# esp-oled-thing.net
KiCad netlist of a schematic drawn in EAGLE
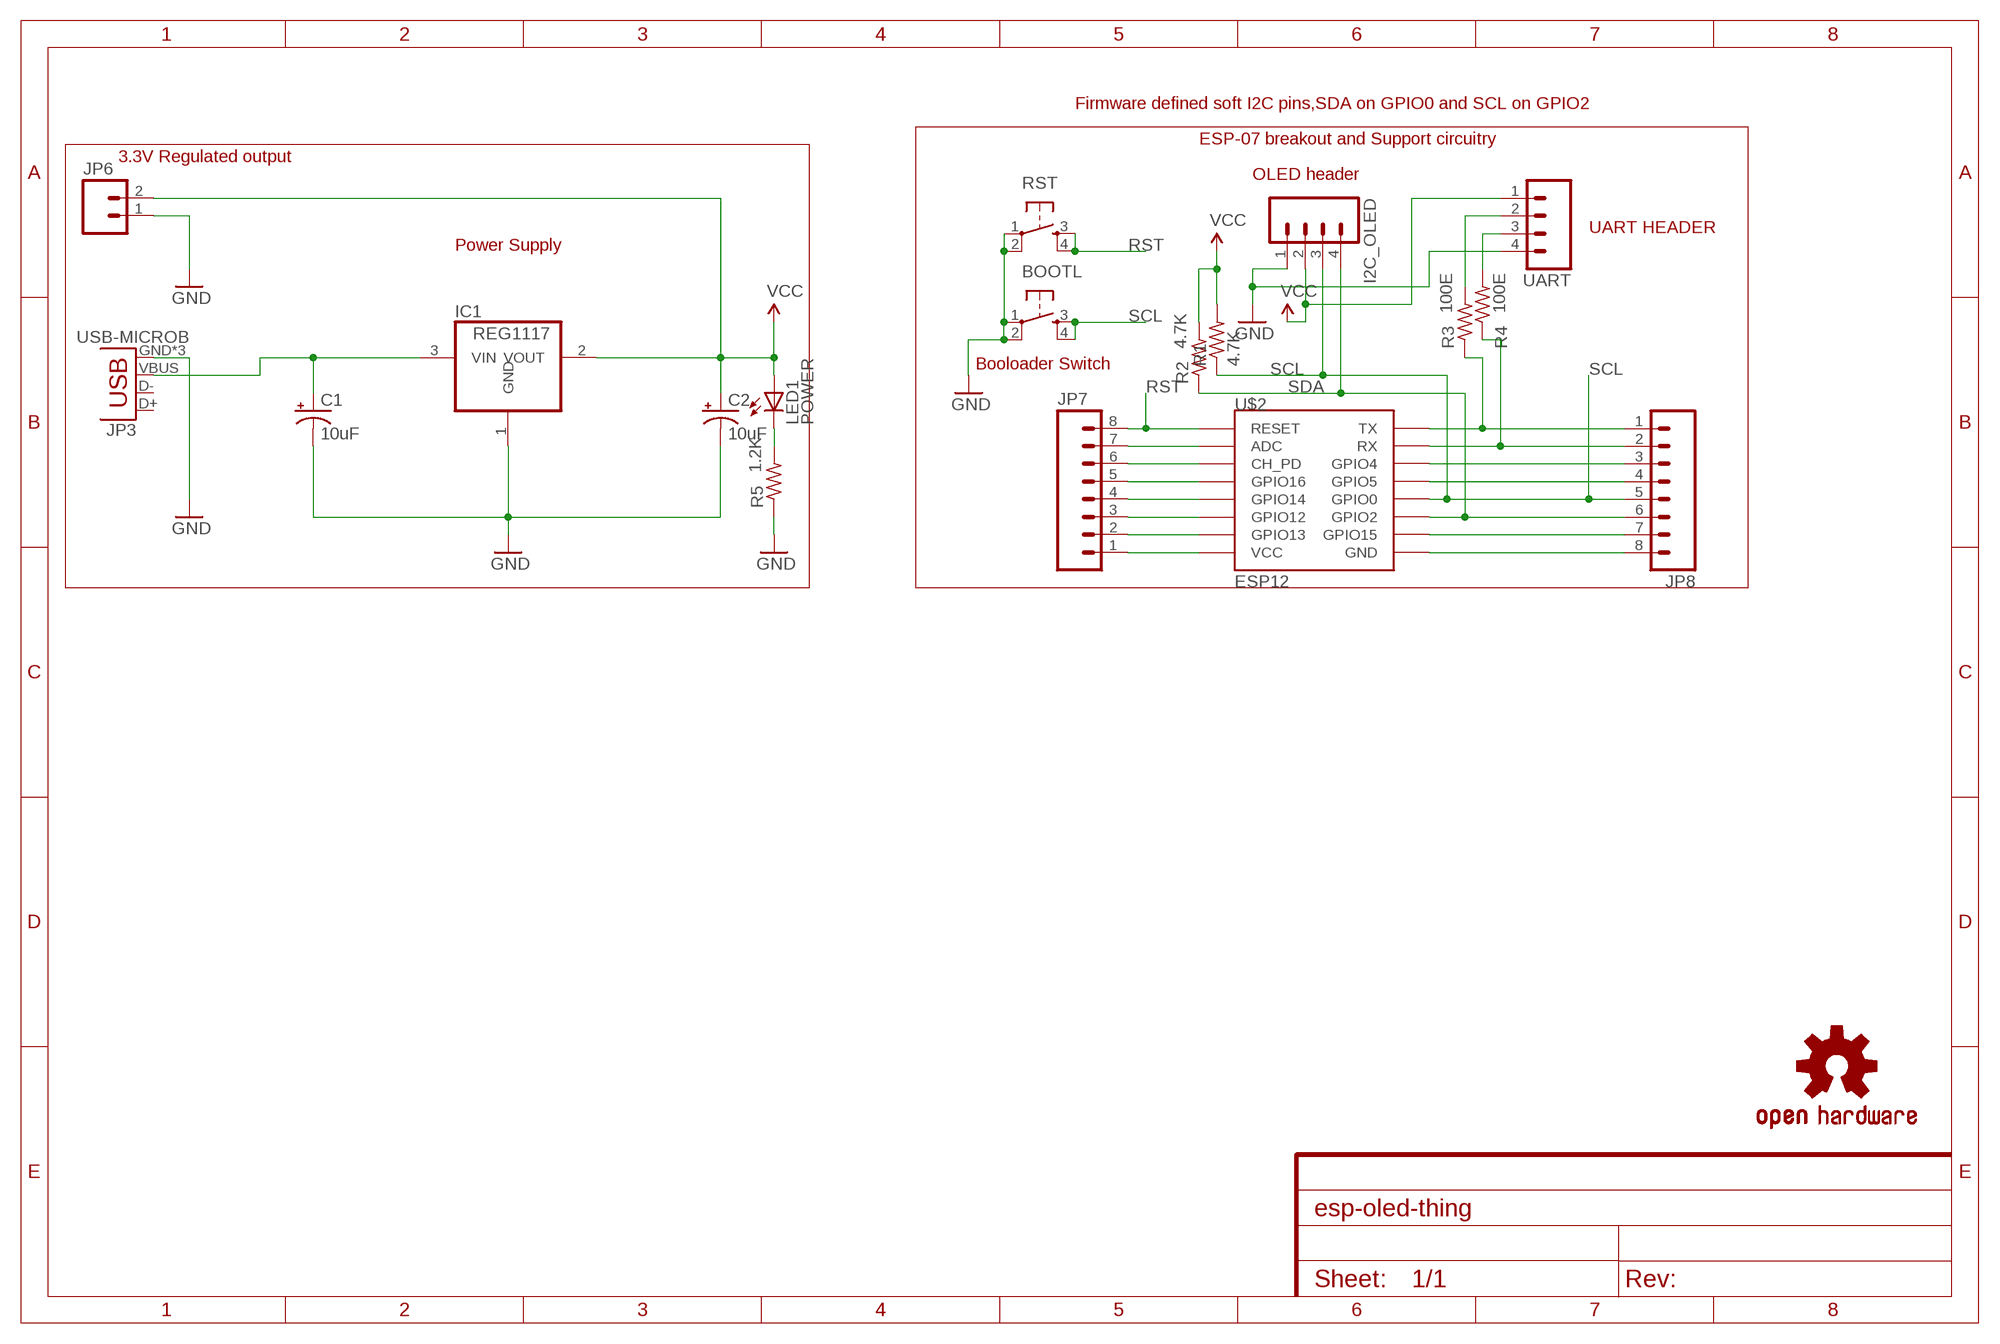
[diagram p0: schematic, sheet 1]

(export (version "E")
  (design (tool "Eeschema 10.0.6"))
  (components
    (comp (ref "BOOTL")
      (value "TAC_SWITCHSMD")
      (footprint "eagle-import:TACTILE_SWITCH_SMD")
      (libsource (lib "eagle-import") (part "TAC_SWITCHSMD"))
    )
    (comp (ref "C1")
      (value "10uF")
      (footprint "eagle-import:EIA3216")
      (libsource (lib "eagle-import") (part "10UF-16V-10%(TANT)"))
    )
    (comp (ref "C2")
      (value "10uF")
      (footprint "eagle-import:EIA3216")
      (libsource (lib "eagle-import") (part "10UF-16V-10%(TANT)"))
    )
    (comp (ref "I2C_OLED")
      (value "M04PTH")
      (footprint "eagle-import:1X04")
      (libsource (lib "eagle-import") (part "M04PTH"))
    )
    (comp (ref "IC1")
      (value "REG1117")
      (footprint "eagle-import:SOT223")
      (libsource (lib "eagle-import") (part "REG1117"))
    )
    (comp (ref "JP3")
      (value "USB-MICROB")
      (footprint "eagle-import:USB-MICROB")
      (libsource (lib "eagle-import") (part "USB-MICROB"))
    )
    (comp (ref "JP6")
      (value "M02JST-PTH-2")
      (footprint "eagle-import:JST-2-PTH")
      (libsource (lib "eagle-import") (part "M02JST-PTH-2"))
    )
    (comp (ref "JP7")
      (value "M081X08")
      (footprint "eagle-import:1X08")
      (libsource (lib "eagle-import") (part "M081X08"))
    )
    (comp (ref "JP8")
      (value "M081X08")
      (footprint "eagle-import:1X08")
      (libsource (lib "eagle-import") (part "M081X08"))
    )
    (comp (ref "LED1")
      (value "POWER")
      (footprint "eagle-import:CHIPLED_0805")
      (libsource (lib "eagle-import") (part "LEDCHIPLED_0805"))
    )
    (comp (ref "R1")
      (value "4.7K")
      (footprint "eagle-import:M0805")
      (libsource (lib "eagle-import") (part "R-US_M0805"))
    )
    (comp (ref "R2")
      (value "4.7K")
      (footprint "eagle-import:M0805")
      (libsource (lib "eagle-import") (part "R-US_M0805"))
    )
    (comp (ref "R3")
      (value "100E")
      (footprint "eagle-import:M0805")
      (libsource (lib "eagle-import") (part "R-US_M0805"))
    )
    (comp (ref "R4")
      (value "100E")
      (footprint "eagle-import:M0805")
      (libsource (lib "eagle-import") (part "R-US_M0805"))
    )
    (comp (ref "R5")
      (value "1.2K")
      (footprint "eagle-import:M0805")
      (libsource (lib "eagle-import") (part "R-US_M0805"))
    )
    (comp (ref "RST")
      (value "TAC_SWITCHSMD")
      (footprint "eagle-import:TACTILE_SWITCH_SMD")
      (libsource (lib "eagle-import") (part "TAC_SWITCHSMD"))
    )
    (comp (ref "U$1")
      (value "OSHW-LOGOS")
      (footprint "eagle-import:OSHW-LOGO-S")
      (libsource (lib "eagle-import") (part "OSHW-LOGOS"))
    )
    (comp (ref "U$2")
      (value "ESP12")
      (footprint "eagle-import:ESP12")
      (libsource (lib "eagle-import") (part "ESP12"))
    )
    (comp (ref "UART")
      (value "M04LONGPADS")
      (footprint "eagle-import:1X04_LONGPADS")
      (libsource (lib "eagle-import") (part "M04LONGPADS"))
    )
  )
  (nets
    (net (code "1") (name "/RST") (class "Default")
      (node (ref "JP7") (pin "8") (pinfunction "8_8") (pintype "passive"))
      (node (ref "RST") (pin "3") (pinfunction "3_3") (pintype "passive"))
      (node (ref "RST") (pin "4") (pinfunction "4_4") (pintype "passive"))
      (node (ref "U$2") (pin "RESET") (pinfunction "RESET_RESET") (pintype "bidirectional"))
    )
    (net (code "2") (name "/SCL") (class "Default")
      (node (ref "BOOTL") (pin "3") (pinfunction "3_3") (pintype "passive"))
      (node (ref "BOOTL") (pin "4") (pinfunction "4_4") (pintype "passive"))
      (node (ref "I2C_OLED") (pin "3") (pinfunction "3_3") (pintype "passive"))
      (node (ref "JP8") (pin "5") (pinfunction "5_5") (pintype "passive"))
      (node (ref "R1") (pin "1") (pinfunction "1_1") (pintype "passive"))
      (node (ref "U$2") (pin "GPIO0") (pinfunction "GPIO0_GPIO0") (pintype "bidirectional"))
    )
    (net (code "3") (name "/SDA") (class "Default")
      (node (ref "I2C_OLED") (pin "4") (pinfunction "4_4") (pintype "passive"))
      (node (ref "JP8") (pin "6") (pinfunction "6_6") (pintype "passive"))
      (node (ref "R2") (pin "1") (pinfunction "1_1") (pintype "passive"))
      (node (ref "U$2") (pin "GPIO2") (pinfunction "GPIO2_GPIO2") (pintype "bidirectional"))
    )
    (net (code "4") (name "GND") (class "Default")
      (node (ref "BOOTL") (pin "1") (pinfunction "1_1") (pintype "passive"))
      (node (ref "BOOTL") (pin "2") (pinfunction "2_2") (pintype "passive"))
      (node (ref "C1") (pin "C") (pinfunction "-_C") (pintype "passive"))
      (node (ref "C2") (pin "C") (pinfunction "-_C") (pintype "passive"))
      (node (ref "I2C_OLED") (pin "1") (pinfunction "1_1") (pintype "passive"))
      (node (ref "IC1") (pin "1") (pinfunction "GND_1") (pintype "power_in"))
      (node (ref "JP3") (pin "GND") (pinfunction "GND_GND") (pintype "bidirectional"))
      (node (ref "JP3") (pin "MT1") (pinfunction "GND_MT1") (pintype "bidirectional"))
      (node (ref "JP3") (pin "MT2") (pinfunction "GND_MT2") (pintype "bidirectional"))
      (node (ref "JP6") (pin "1") (pinfunction "1_1") (pintype "passive"))
      (node (ref "R5") (pin "1") (pinfunction "1_1") (pintype "passive"))
      (node (ref "RST") (pin "1") (pinfunction "1_1") (pintype "passive"))
      (node (ref "RST") (pin "2") (pinfunction "2_2") (pintype "passive"))
      (node (ref "UART") (pin "4") (pinfunction "4_4") (pintype "passive"))
    )
    (net (code "5") (name "Net-(C1-+)") (class "Default")
      (node (ref "C1") (pin "A") (pinfunction "+_A") (pintype "passive"))
      (node (ref "IC1") (pin "3") (pinfunction "VIN_3") (pintype "input"))
      (node (ref "JP3") (pin "VBUS") (pinfunction "VBUS_VBUS") (pintype "bidirectional"))
    )
    (net (code "6") (name "Net-(JP7-Pad1)") (class "Default")
      (node (ref "JP7") (pin "1") (pinfunction "1_1") (pintype "passive"))
      (node (ref "U$2") (pin "VCC") (pinfunction "VCC_VCC") (pintype "bidirectional"))
    )
    (net (code "7") (name "Net-(JP7-Pad2)") (class "Default")
      (node (ref "JP7") (pin "2") (pinfunction "2_2") (pintype "passive"))
      (node (ref "U$2") (pin "GPIO13") (pinfunction "GPIO13_GPIO13") (pintype "bidirectional"))
    )
    (net (code "8") (name "Net-(JP7-Pad3)") (class "Default")
      (node (ref "JP7") (pin "3") (pinfunction "3_3") (pintype "passive"))
      (node (ref "U$2") (pin "GPIO12") (pinfunction "GPIO12_GPIO12") (pintype "bidirectional"))
    )
    (net (code "9") (name "Net-(JP7-Pad4)") (class "Default")
      (node (ref "JP7") (pin "4") (pinfunction "4_4") (pintype "passive"))
      (node (ref "U$2") (pin "GPIO14") (pinfunction "GPIO14_GPIO14") (pintype "bidirectional"))
    )
    (net (code "10") (name "Net-(JP7-Pad5)") (class "Default")
      (node (ref "JP7") (pin "5") (pinfunction "5_5") (pintype "passive"))
      (node (ref "U$2") (pin "GPIO16") (pinfunction "GPIO16_GPIO16") (pintype "bidirectional"))
    )
    (net (code "11") (name "Net-(JP7-Pad6)") (class "Default")
      (node (ref "JP7") (pin "6") (pinfunction "6_6") (pintype "passive"))
      (node (ref "U$2") (pin "CH_PD") (pinfunction "CH_PD_CH_PD") (pintype "bidirectional"))
    )
    (net (code "12") (name "Net-(JP7-Pad7)") (class "Default")
      (node (ref "JP7") (pin "7") (pinfunction "7_7") (pintype "passive"))
      (node (ref "U$2") (pin "ADC") (pinfunction "ADC_ADC") (pintype "bidirectional"))
    )
    (net (code "13") (name "Net-(JP8-Pad1)") (class "Default")
      (node (ref "JP8") (pin "1") (pinfunction "1_1") (pintype "passive"))
      (node (ref "R3") (pin "1") (pinfunction "1_1") (pintype "passive"))
      (node (ref "U$2") (pin "TX") (pinfunction "TX_TX") (pintype "bidirectional"))
    )
    (net (code "14") (name "Net-(JP8-Pad2)") (class "Default")
      (node (ref "JP8") (pin "2") (pinfunction "2_2") (pintype "passive"))
      (node (ref "R4") (pin "1") (pinfunction "1_1") (pintype "passive"))
      (node (ref "U$2") (pin "RX") (pinfunction "RX_RX") (pintype "bidirectional"))
    )
    (net (code "15") (name "Net-(JP8-Pad3)") (class "Default")
      (node (ref "JP8") (pin "3") (pinfunction "3_3") (pintype "passive"))
      (node (ref "U$2") (pin "GPIO4") (pinfunction "GPIO4_GPIO4") (pintype "bidirectional"))
    )
    (net (code "16") (name "Net-(JP8-Pad4)") (class "Default")
      (node (ref "JP8") (pin "4") (pinfunction "4_4") (pintype "passive"))
      (node (ref "U$2") (pin "GPIO5") (pinfunction "GPIO5_GPIO5") (pintype "bidirectional"))
    )
    (net (code "17") (name "Net-(JP8-Pad7)") (class "Default")
      (node (ref "JP8") (pin "7") (pinfunction "7_7") (pintype "passive"))
      (node (ref "U$2") (pin "GPIO15") (pinfunction "GPIO15_GPIO15") (pintype "bidirectional"))
    )
    (net (code "18") (name "Net-(JP8-Pad8)") (class "Default")
      (node (ref "JP8") (pin "8") (pinfunction "8_8") (pintype "passive"))
      (node (ref "U$2") (pin "GND") (pinfunction "GND_GND") (pintype "bidirectional"))
    )
    (net (code "19") (name "Net-(LED1-PadC)") (class "Default")
      (node (ref "LED1") (pin "C") (pinfunction "C_C") (pintype "passive"))
      (node (ref "R5") (pin "2") (pinfunction "2_2") (pintype "passive"))
    )
    (net (code "20") (name "Net-(R3-Pad2)") (class "Default")
      (node (ref "R3") (pin "2") (pinfunction "2_2") (pintype "passive"))
      (node (ref "UART") (pin "2") (pinfunction "2_2") (pintype "passive"))
    )
    (net (code "21") (name "Net-(R4-Pad2)") (class "Default")
      (node (ref "R4") (pin "2") (pinfunction "2_2") (pintype "passive"))
      (node (ref "UART") (pin "3") (pinfunction "3_3") (pintype "passive"))
    )
    (net (code "22") (name "VCC") (class "Default")
      (node (ref "C2") (pin "A") (pinfunction "+_A") (pintype "passive"))
      (node (ref "I2C_OLED") (pin "2") (pinfunction "2_2") (pintype "passive"))
      (node (ref "IC1") (pin "2") (pinfunction "VOUT_2") (pintype "output"))
      (node (ref "JP6") (pin "2") (pinfunction "2_2") (pintype "passive"))
      (node (ref "LED1") (pin "A") (pinfunction "A_A") (pintype "passive"))
      (node (ref "R1") (pin "2") (pinfunction "2_2") (pintype "passive"))
      (node (ref "R2") (pin "2") (pinfunction "2_2") (pintype "passive"))
      (node (ref "UART") (pin "1") (pinfunction "1_1") (pintype "passive"))
    )
    (net (code "23") (name "unconnected-(JP3-PadD+)") (class "Default")
      (node (ref "JP3") (pin "D+") (pinfunction "D+_D+") (pintype "bidirectional"))
    )
    (net (code "24") (name "unconnected-(JP3-PadD-)") (class "Default")
      (node (ref "JP3") (pin "D-") (pinfunction "D-_D-") (pintype "bidirectional"))
    )
  )
)
